# MCU.net
KiCad netlist of a schematic drawn in Altium Designer
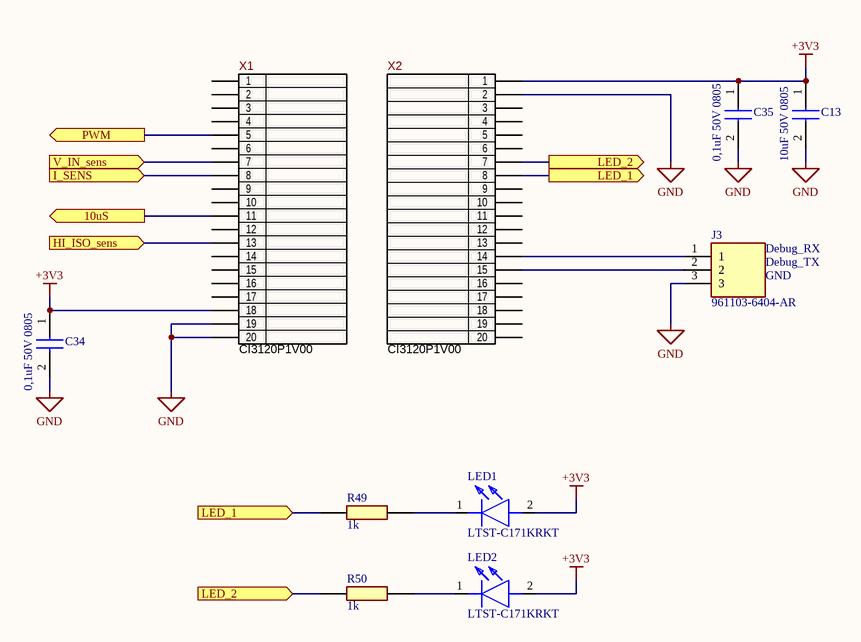
[diagram p0: MCU.SchDoc]

(export (version "E")
  (design (tool "Eeschema 10.0.6"))
  (components
    (comp (ref "C13")
      (value "10uF 50V 0805")
      (footprint "CAPC2012X90N")
      (description "Capacitor")
      (libsource (lib "Boost") (part "MCMT21N470F250CT"))
    )
    (comp (ref "C34")
      (value "0,1uF 50V 0805")
      (footprint "SamacSys:CAPC2012X90N")
      (description "Capacitor")
      (libsource (lib "*") (part "MCMT21N470F250CT"))
    )
    (comp (ref "C35")
      (value "0,1uF 50V 0805")
      (footprint "SamacSys:CAPC2012X90N")
      (description "Capacitor")
      (libsource (lib "*") (part "MCMT21N470F250CT"))
    )
    (comp (ref "J3")
      (value "961103-6404-AR")
      (footprint "SamacSys:HDRV3W64P0X254_1X3_762X250X1050P")
      (description "Connector")
      (fields (field (name "MOUSER PART NUMBER") "517-9611036404AR"))
      (libsource (lib "*") (part "961103-6404-AR"))
    )
    (comp (ref "LED1")
      (value "LTST-C171KRKT")
      (footprint "SamacSys:LEDM2012X90N")
      (description "LED")
      (fields (field (name "MOUSER PART NUMBER") "859-LTST-C171KRKT"))
      (libsource (lib "*") (part "LTST-C171KRKT"))
    )
    (comp (ref "LED2")
      (value "LTST-C171KRKT")
      (footprint "SamacSys:LEDM2012X90N")
      (description "LED")
      (fields (field (name "MOUSER PART NUMBER") "859-LTST-C171KRKT"))
      (libsource (lib "*") (part "LTST-C171KRKT"))
    )
    (comp (ref "R49")
      (value "1k")
      (footprint "RESC2013X65N")
      (description "Resistor")
      (libsource (lib "SamacSys") (part "ERJP06J822V"))
    )
    (comp (ref "R50")
      (value "1k")
      (footprint "RESC2013X65N")
      (description "Resistor")
      (libsource (lib "SamacSys") (part "ERJP06J822V"))
    )
    (comp (ref "X1")
      (value "WH-20S")
      (footprint "WF-20S")
      (description "WH Series 2.54mm Wire to Board Straight DIP Type Headers, 20 Pin")
      (fields (field (name "PART NUMBER") "CI3120P1V00") (field (name "MANUFACTURER") "CviLux"))
      (libsource (lib "AjaxLibrary") (part "General-20-Pin"))
    )
    (comp (ref "X2")
      (value "WH-20S")
      (footprint "WF-20S")
      (description "WH Series 2.54mm Wire to Board Straight DIP Type Headers, 20 Pin")
      (fields (field (name "PART NUMBER") "CI3120P1V00") (field (name "MANUFACTURER") "CviLux"))
      (libsource (lib "AjaxLibrary") (part "General-20-Pin"))
    )
  )
  (nets
    (net (code "1") (name "+3V3") (class "Default")
      (node (ref "C13") (pin "1") (pinfunction "1_1") (pintype "passive"))
      (node (ref "C34") (pin "1") (pinfunction "1_1") (pintype "passive"))
      (node (ref "C35") (pin "1") (pinfunction "1_1") (pintype "passive"))
      (node (ref "LED1") (pin "2") (pinfunction "A_2") (pintype "passive"))
      (node (ref "LED2") (pin "2") (pinfunction "A_2") (pintype "passive"))
      (node (ref "X1") (pin "18") (pinfunction "18_18") (pintype "passive"))
      (node (ref "X2") (pin "1") (pinfunction "1_1") (pintype "passive"))
    )
    (net (code "2") (name "/10uS") (class "Default")
      (node (ref "X1") (pin "11") (pinfunction "11_11") (pintype "passive"))
    )
    (net (code "3") (name "/HI_ISO_sens") (class "Default")
      (node (ref "X1") (pin "13") (pinfunction "13_13") (pintype "passive"))
    )
    (net (code "4") (name "/I_SENS") (class "Default")
      (node (ref "X1") (pin "8") (pinfunction "8_8") (pintype "passive"))
    )
    (net (code "5") (name "/LED_1") (class "Default")
      (node (ref "R49") (pin "2") (pinfunction "2_2") (pintype "passive"))
      (node (ref "X2") (pin "8") (pinfunction "8_8") (pintype "passive"))
    )
    (net (code "6") (name "/LED_2") (class "Default")
      (node (ref "R50") (pin "2") (pinfunction "2_2") (pintype "passive"))
      (node (ref "X2") (pin "7") (pinfunction "7_7") (pintype "passive"))
    )
    (net (code "7") (name "/PWM") (class "Default")
      (node (ref "X1") (pin "5") (pinfunction "5_5") (pintype "passive"))
    )
    (net (code "8") (name "/V_IN_sens") (class "Default")
      (node (ref "X1") (pin "7") (pinfunction "7_7") (pintype "passive"))
    )
    (net (code "9") (name "GND") (class "Default")
      (node (ref "C13") (pin "2") (pinfunction "2_2") (pintype "passive"))
      (node (ref "C34") (pin "2") (pinfunction "2_2") (pintype "passive"))
      (node (ref "C35") (pin "2") (pinfunction "2_2") (pintype "passive"))
      (node (ref "J3") (pin "3") (pinfunction "3_3") (pintype "passive"))
      (node (ref "X1") (pin "19") (pinfunction "19_19") (pintype "passive"))
      (node (ref "X1") (pin "20") (pinfunction "20_20") (pintype "passive"))
      (node (ref "X2") (pin "2") (pinfunction "2_2") (pintype "passive"))
    )
    (net (code "10") (name "Net-(J3-Pad1)") (class "Default")
      (node (ref "J3") (pin "1") (pinfunction "1_1") (pintype "passive"))
      (node (ref "X2") (pin "14") (pinfunction "14_14") (pintype "passive"))
    )
    (net (code "11") (name "Net-(J3-Pad2)") (class "Default")
      (node (ref "J3") (pin "2") (pinfunction "2_2") (pintype "passive"))
      (node (ref "X2") (pin "15") (pinfunction "15_15") (pintype "passive"))
    )
    (net (code "12") (name "Net-(LED1-K)") (class "Default")
      (node (ref "LED1") (pin "1") (pinfunction "K_1") (pintype "passive"))
      (node (ref "R49") (pin "1") (pinfunction "1_1") (pintype "passive"))
    )
    (net (code "13") (name "Net-(LED2-K)") (class "Default")
      (node (ref "LED2") (pin "1") (pinfunction "K_1") (pintype "passive"))
      (node (ref "R50") (pin "1") (pinfunction "1_1") (pintype "passive"))
    )
    (net (code "14") (name "unconnected-(X1-Pad1)") (class "Default")
      (node (ref "X1") (pin "1") (pinfunction "1_1") (pintype "passive"))
    )
    (net (code "15") (name "unconnected-(X1-Pad2)") (class "Default")
      (node (ref "X1") (pin "2") (pinfunction "2_2") (pintype "passive"))
    )
    (net (code "16") (name "unconnected-(X1-Pad3)") (class "Default")
      (node (ref "X1") (pin "3") (pinfunction "3_3") (pintype "passive"))
    )
    (net (code "17") (name "unconnected-(X1-Pad4)") (class "Default")
      (node (ref "X1") (pin "4") (pinfunction "4_4") (pintype "passive"))
    )
    (net (code "18") (name "unconnected-(X1-Pad6)") (class "Default")
      (node (ref "X1") (pin "6") (pinfunction "6_6") (pintype "passive"))
    )
    (net (code "19") (name "unconnected-(X1-Pad9)") (class "Default")
      (node (ref "X1") (pin "9") (pinfunction "9_9") (pintype "passive"))
    )
    (net (code "20") (name "unconnected-(X1-Pad10)") (class "Default")
      (node (ref "X1") (pin "10") (pinfunction "10_10") (pintype "passive"))
    )
    (net (code "21") (name "unconnected-(X1-Pad12)") (class "Default")
      (node (ref "X1") (pin "12") (pinfunction "12_12") (pintype "passive"))
    )
    (net (code "22") (name "unconnected-(X1-Pad14)") (class "Default")
      (node (ref "X1") (pin "14") (pinfunction "14_14") (pintype "passive"))
    )
    (net (code "23") (name "unconnected-(X1-Pad15)") (class "Default")
      (node (ref "X1") (pin "15") (pinfunction "15_15") (pintype "passive"))
    )
    (net (code "24") (name "unconnected-(X1-Pad16)") (class "Default")
      (node (ref "X1") (pin "16") (pinfunction "16_16") (pintype "passive"))
    )
    (net (code "25") (name "unconnected-(X1-Pad17)") (class "Default")
      (node (ref "X1") (pin "17") (pinfunction "17_17") (pintype "passive"))
    )
    (net (code "26") (name "unconnected-(X2-Pad3)") (class "Default")
      (node (ref "X2") (pin "3") (pinfunction "3_3") (pintype "passive"))
    )
    (net (code "27") (name "unconnected-(X2-Pad4)") (class "Default")
      (node (ref "X2") (pin "4") (pinfunction "4_4") (pintype "passive"))
    )
    (net (code "28") (name "unconnected-(X2-Pad5)") (class "Default")
      (node (ref "X2") (pin "5") (pinfunction "5_5") (pintype "passive"))
    )
    (net (code "29") (name "unconnected-(X2-Pad6)") (class "Default")
      (node (ref "X2") (pin "6") (pinfunction "6_6") (pintype "passive"))
    )
    (net (code "30") (name "unconnected-(X2-Pad9)") (class "Default")
      (node (ref "X2") (pin "9") (pinfunction "9_9") (pintype "passive"))
    )
    (net (code "31") (name "unconnected-(X2-Pad10)") (class "Default")
      (node (ref "X2") (pin "10") (pinfunction "10_10") (pintype "passive"))
    )
    (net (code "32") (name "unconnected-(X2-Pad11)") (class "Default")
      (node (ref "X2") (pin "11") (pinfunction "11_11") (pintype "passive"))
    )
    (net (code "33") (name "unconnected-(X2-Pad12)") (class "Default")
      (node (ref "X2") (pin "12") (pinfunction "12_12") (pintype "passive"))
    )
    (net (code "34") (name "unconnected-(X2-Pad13)") (class "Default")
      (node (ref "X2") (pin "13") (pinfunction "13_13") (pintype "passive"))
    )
    (net (code "35") (name "unconnected-(X2-Pad16)") (class "Default")
      (node (ref "X2") (pin "16") (pinfunction "16_16") (pintype "passive"))
    )
    (net (code "36") (name "unconnected-(X2-Pad17)") (class "Default")
      (node (ref "X2") (pin "17") (pinfunction "17_17") (pintype "passive"))
    )
    (net (code "37") (name "unconnected-(X2-Pad18)") (class "Default")
      (node (ref "X2") (pin "18") (pinfunction "18_18") (pintype "passive"))
    )
    (net (code "38") (name "unconnected-(X2-Pad19)") (class "Default")
      (node (ref "X2") (pin "19") (pinfunction "19_19") (pintype "passive"))
    )
    (net (code "39") (name "unconnected-(X2-Pad20)") (class "Default")
      (node (ref "X2") (pin "20") (pinfunction "20_20") (pintype "passive"))
    )
  )
)
